# Urukul_FPGA_Config.net
KiCad netlist of a schematic drawn in Altium Designer
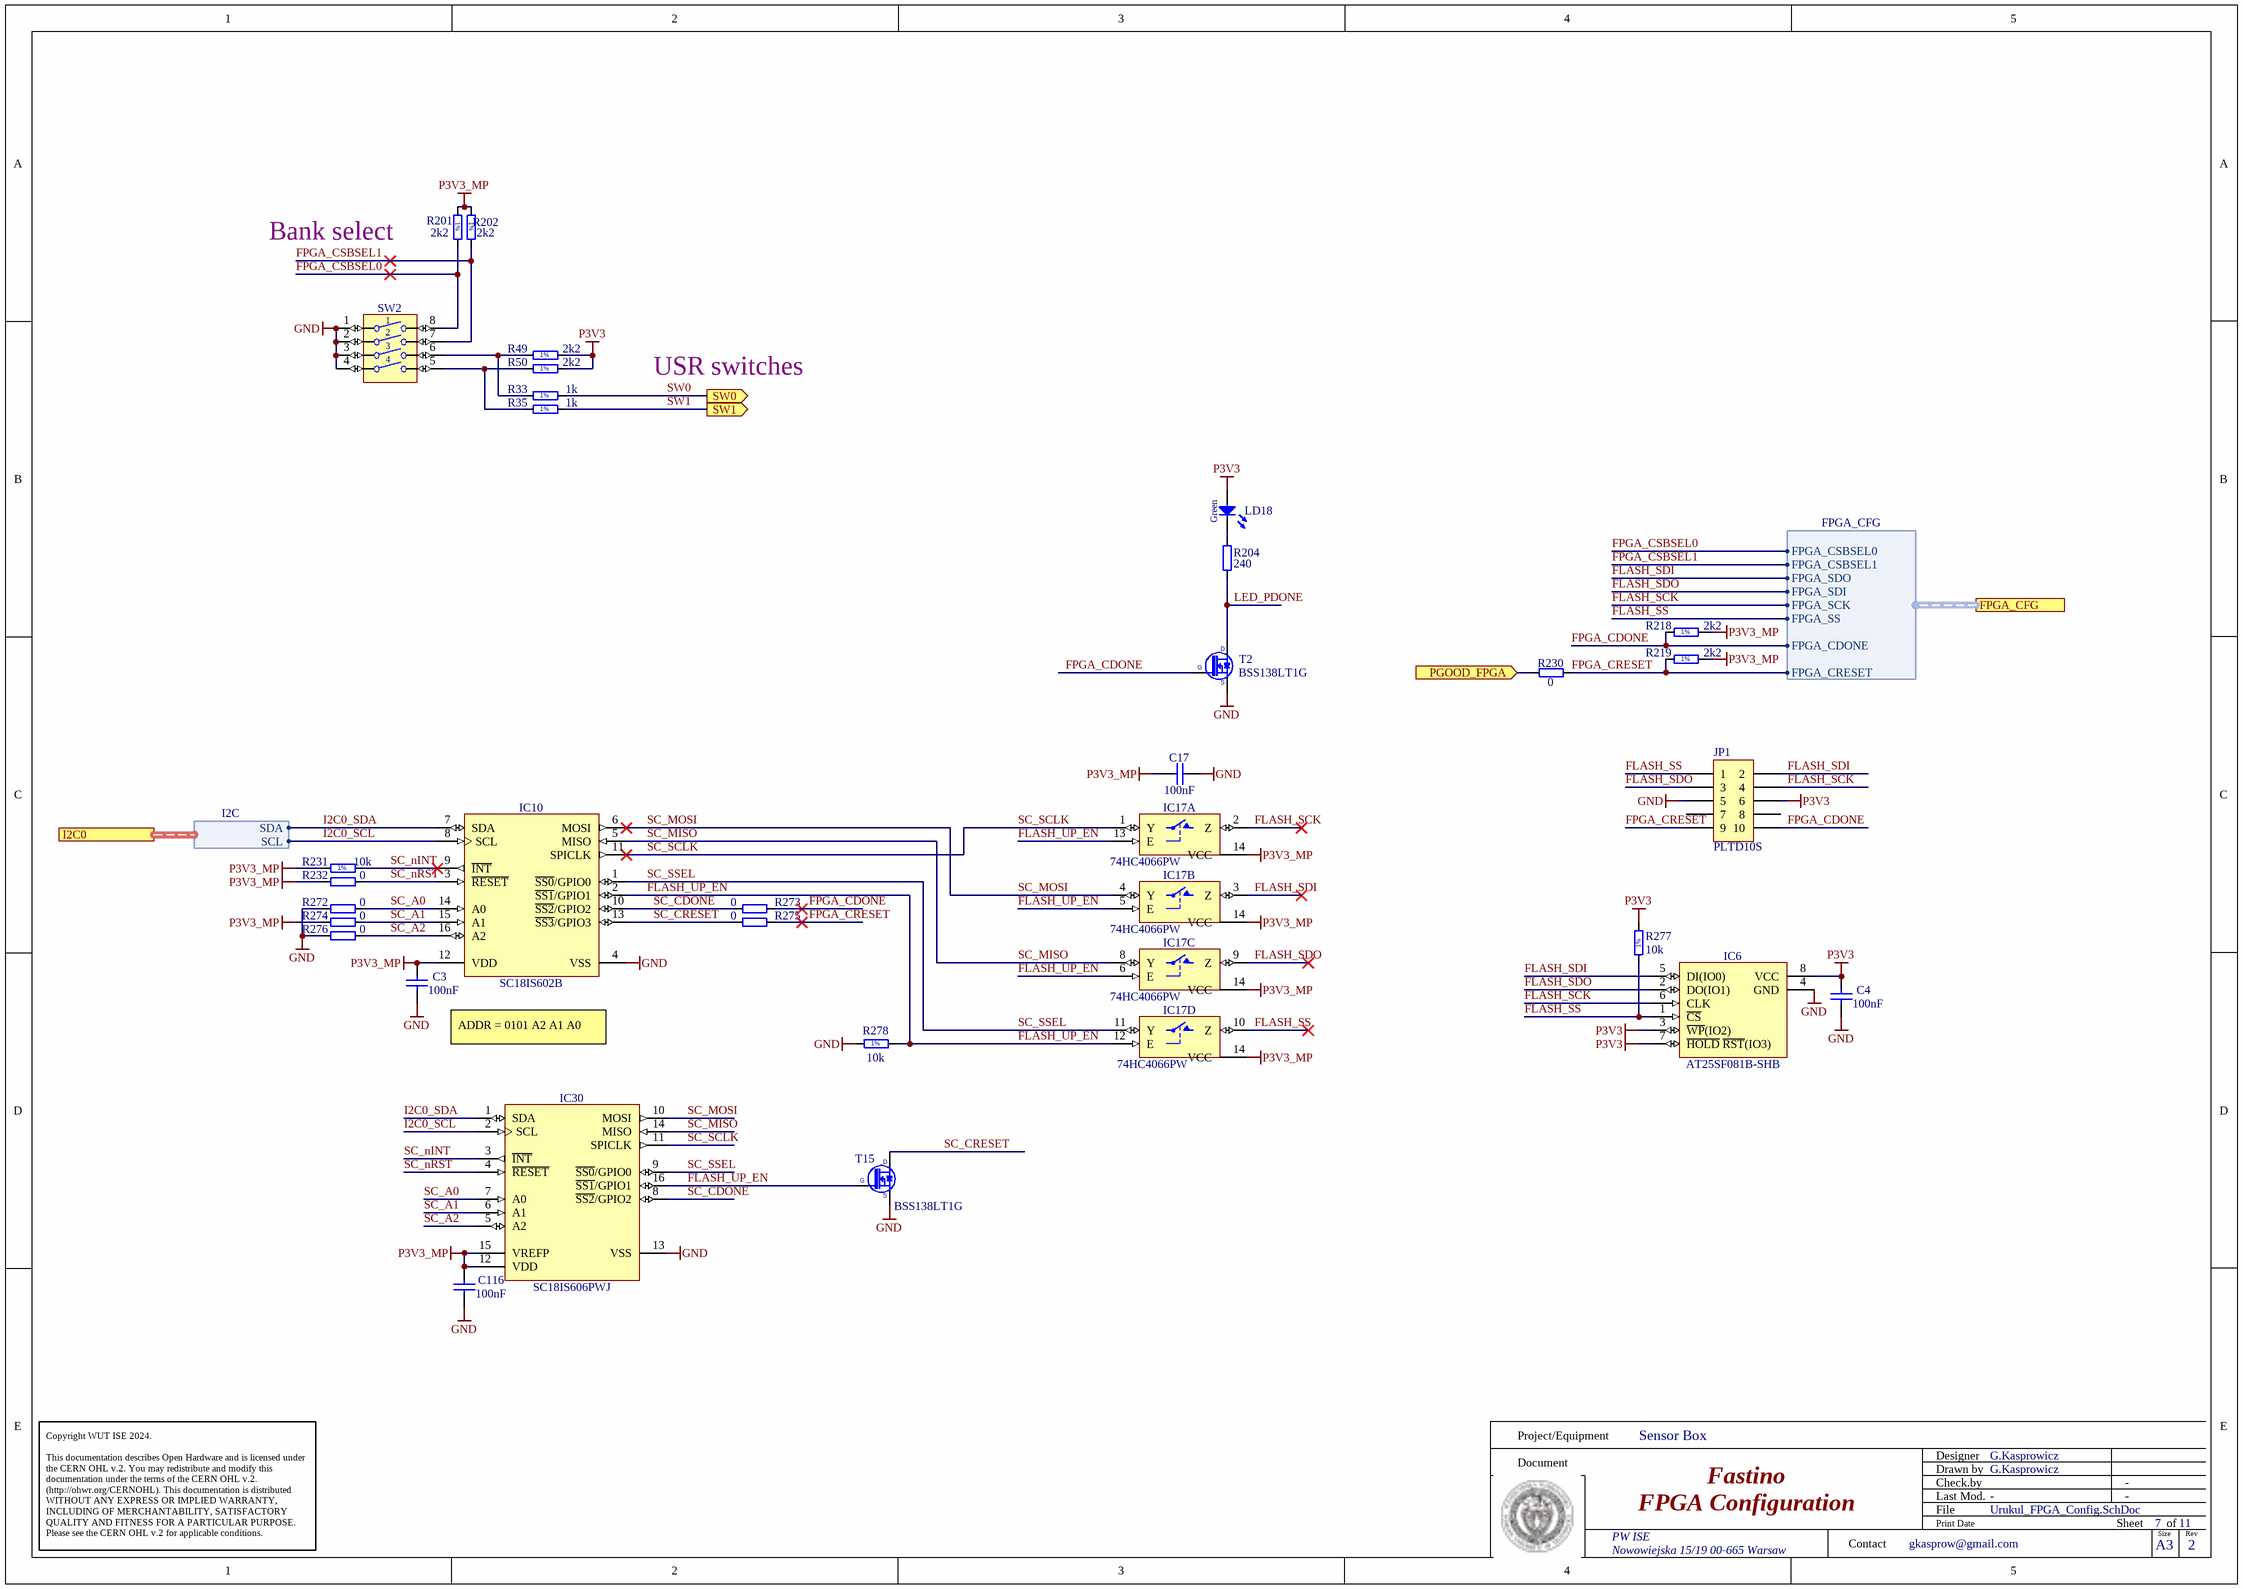
[diagram p0: Urukul_FPGA_Config.SchDoc]

(export (version "E")
  (design (tool "Eeschema 10.0.6"))
  (components
    (comp (ref "C3")
      (value "100nF")
      (footprint "CAPC1005X55N")
      (description "Non-polarised capacitor")
      (fields
        (field (name "PART NUMBER") "CC0402_100NF_16V_10%_X5R")
        (field (name "VOLTAGE") "16V")
        (field (name "AUTHOR") "CERN DEM JLC")
      )
      (libsource (lib "Capacitors") (part "Capacitor - non polarized"))
    )
    (comp (ref "C4")
      (value "100nF")
      (footprint "CAPC1005X55N")
      (description "Non-polarised capacitor")
      (fields
        (field (name "PART NUMBER") "CC0402_100NF_16V_10%_X5R")
        (field (name "VOLTAGE") "16V")
        (field (name "AUTHOR") "CERN DEM JLC")
      )
      (libsource (lib "Capacitors") (part "Capacitor - non polarized"))
    )
    (comp (ref "C17")
      (value "100nF")
      (footprint "CAPC1005X55N")
      (description "Non-polarised capacitor")
      (fields
        (field (name "PART NUMBER") "CC0402_100NF_16V_10%_X5R")
        (field (name "VOLTAGE") "16V")
        (field (name "AUTHOR") "CERN DEM JLC")
      )
      (libsource (lib "Capacitors") (part "Capacitor - non polarized"))
    )
    (comp (ref "C116")
      (value "100nF")
      (footprint "CAPC1005X55N")
      (description "Non-polarised capacitor")
      (fields
        (field (name "PART NUMBER") "CC0402_100NF_16V_10%_X5R")
        (field (name "VOLTAGE") "16V")
        (field (name "AUTHOR") "CERN DEM JLC")
      )
      (libsource (lib "Capacitors") (part "Capacitor - non polarized"))
    )
    (comp (ref "IC6")
      (value "AT25SF081B-SHB")
      (footprint "SOIC127P790X216-8N")
      (description "8M-bit Serial Flash Memory with uniform 4KB sectors and Dual/Quad SPI and QPI")
      (fields (field (name "MANUFACTURER") "Renesas") (field (name "AUTHOR") "GK"))
      (libsource (lib "ICS-logic") (part "MEM_AT25SF081B-SHB"))
    )
    (comp (ref "IC10")
      (value "SC18IS602B")
      (footprint "SOP65P640X110-16N")
      (description "I2C-bus to SPI bridge")
      (fields (field (name "MANUFACTURER") "NXP SEMICONDUCTORS") (field (name "AUTHOR") "CERN DEM MR"))
      (libsource (lib "ICs And Semiconductors") (part "SC18IS602B"))
    )
    (comp (ref "IC17")
      (value "74HC4066PW")
      (footprint "SOP65P640X110-14N")
      (fields (field (name "MANUFACTURER") "NXP SEMICONDUCTORS") (field (name "AUTHOR") "CERN DEM JLC"))
      (libsource (lib "ICs And Semiconductors") (part "4066"))
    )
    (comp (ref "IC30")
      (value "SC18IS606PWJ")
      (footprint "SOP65P640X110-16N")
      (description "I2C-bus to SPI bridge")
      (fields (field (name "MANUFACTURER") "NXP SEMICONDUCTORS") (field (name "AUTHOR") "GK"))
      (libsource (lib "ICS-logic") (part "SC18IS606PWJ"))
    )
    (comp (ref "JP1")
      (value "PLTD10S")
      (footprint "PLTD10S")
      (description "Goldpin 2.54mm, male header")
      (fields (field (name "MANUFACTURER") "Maritex"))
      (libsource (lib "LIBRARY_SCH") (part "CON_2x5 2.54 male SMT"))
    )
    (comp (ref "LD18")
      (value "Green")
      (footprint "LED_AVAGO_HSME-C120")
      (description "LED Green 1C 2A")
      (fields
        (field (name "PART NUMBER") "LED_AVAGO_HSME-C120")
        (field (name "MANUFACTURER") "AVAGO TECHNOLOGIES")
        (field (name "AUTHOR") "CERN DEM JMW")
      )
      (libsource (lib "ICs And Semiconductors") (part "LED Green 1C 2A"))
    )
    (comp (ref "R33")
      (value "1k")
      (footprint "RESC1005X40N")
      (description "Resistor - 1%")
      (fields
        (field (name "PART NUMBER") "R0402_1K_1%_0.0625W_100PPM")
        (field (name "POWER") "0.0625W")
        (field (name "AUTHOR") "CERN DEM JLC")
      )
      (libsource (lib "Resistors") (part "Resistor - 1%"))
    )
    (comp (ref "R35")
      (value "1k")
      (footprint "RESC1005X40N")
      (description "Resistor - 1%")
      (fields
        (field (name "PART NUMBER") "R0402_1K_1%_0.0625W_100PPM")
        (field (name "POWER") "0.0625W")
        (field (name "AUTHOR") "CERN DEM JLC")
      )
      (libsource (lib "Resistors") (part "Resistor - 1%"))
    )
    (comp (ref "R49")
      (value "2k2")
      (footprint "RESC1005X40N")
      (description "Resistor - 1%")
      (fields
        (field (name "PART NUMBER") "R0402_2K2_1%_0.0625W_100PPM")
        (field (name "POWER") "0.0625W")
        (field (name "AUTHOR") "CERN DEM JLC")
      )
      (libsource (lib "Resistors") (part "Resistor - 1%"))
    )
    (comp (ref "R50")
      (value "2k2")
      (footprint "RESC1005X40N")
      (description "Resistor - 1%")
      (fields
        (field (name "PART NUMBER") "R0402_2K2_1%_0.0625W_100PPM")
        (field (name "POWER") "0.0625W")
        (field (name "AUTHOR") "CERN DEM JLC")
      )
      (libsource (lib "Resistors") (part "Resistor - 1%"))
    )
    (comp (ref "R201")
      (value "2k2")
      (footprint "RESC1005X40N")
      (description "Resistor - 1%")
      (fields
        (field (name "PART NUMBER") "R0402_2K2_1%_0.0625W_100PPM")
        (field (name "POWER") "0.0625W")
        (field (name "AUTHOR") "CERN DEM JLC")
      )
      (libsource (lib "Resistors") (part "Resistor - 1%"))
    )
    (comp (ref "R202")
      (value "2k2")
      (footprint "RESC1005X40N")
      (description "Resistor - 1%")
      (fields
        (field (name "PART NUMBER") "R0402_2K2_1%_0.0625W_100PPM")
        (field (name "POWER") "0.0625W")
        (field (name "AUTHOR") "CERN DEM JLC")
      )
      (libsource (lib "Resistors") (part "Resistor - 1%"))
    )
    (comp (ref "R204")
      (value "240")
      (footprint "RESC1005X40N")
      (description "Resistor - 1%")
      (fields
        (field (name "PART NUMBER") "R0402_240R_1%_0.0625W_100PPM")
        (field (name "POWER") "0.0625W")
        (field (name "AUTHOR") "CERN DEM JLC")
      )
      (libsource (lib "Resistors") (part "Resistor - 1%"))
    )
    (comp (ref "R218")
      (value "2k2")
      (footprint "RESC1005X40N")
      (description "Resistor - 1%")
      (fields
        (field (name "PART NUMBER") "R0402_2K2_1%_0.0625W_100PPM")
        (field (name "POWER") "0.0625W")
        (field (name "AUTHOR") "CERN DEM JLC")
      )
      (libsource (lib "Resistors") (part "Resistor - 1%"))
    )
    (comp (ref "R219")
      (value "2k2")
      (footprint "RESC1005X40N")
      (description "Resistor - 1%")
      (fields
        (field (name "PART NUMBER") "R0402_2K2_1%_0.0625W_100PPM")
        (field (name "POWER") "0.0625W")
        (field (name "AUTHOR") "CERN DEM JLC")
      )
      (libsource (lib "Resistors") (part "Resistor - 1%"))
    )
    (comp (ref "R230")
      (value "0")
      (footprint "RESC1005X40N")
      (description "Resistor")
      (fields
        (field (name "PART NUMBER") "R0402_0R_JUMPER")
        (field (name "MANUFACTURER") "GENERIC")
        (field (name "AUTHOR") "CERN DEM JLC")
      )
      (libsource (lib "Resistors") (part "Resistor"))
    )
    (comp (ref "R231")
      (value "10k")
      (footprint "RESC1005X40N")
      (description "Resistor - 1%")
      (fields
        (field (name "PART NUMBER") "R0402_10K_1%_0.0625W_100PPM")
        (field (name "POWER") "0.0625W")
        (field (name "AUTHOR") "CERN DEM JLC")
      )
      (libsource (lib "Resistors") (part "Resistor - 1%"))
    )
    (comp (ref "R232")
      (value "0")
      (footprint "RESC1005X40N")
      (description "Resistor")
      (fields
        (field (name "PART NUMBER") "R0402_0R_JUMPER")
        (field (name "MANUFACTURER") "GENERIC")
        (field (name "AUTHOR") "CERN DEM JLC")
      )
      (libsource (lib "Resistors") (part "Resistor"))
    )
    (comp (ref "R272")
      (value "0")
      (footprint "RESC1005X40N")
      (description "Resistor")
      (fields
        (field (name "PART NUMBER") "R0402_0R_JUMPER")
        (field (name "MANUFACTURER") "GENERIC")
        (field (name "AUTHOR") "CERN DEM JLC")
      )
      (libsource (lib "Resistors") (part "Resistor"))
    )
    (comp (ref "R273")
      (value "0")
      (footprint "RESC1005X40N")
      (description "Resistor")
      (fields
        (field (name "PART NUMBER") "R0402_0R_JUMPER")
        (field (name "MANUFACTURER") "GENERIC")
        (field (name "AUTHOR") "CERN DEM JLC")
      )
      (libsource (lib "Resistors") (part "Resistor"))
    )
    (comp (ref "R274")
      (value "0")
      (footprint "RESC1005X40N")
      (description "Resistor")
      (fields
        (field (name "PART NUMBER") "R0402_0R_JUMPER")
        (field (name "MANUFACTURER") "GENERIC")
        (field (name "AUTHOR") "CERN DEM JLC")
      )
      (libsource (lib "Resistors") (part "Resistor"))
    )
    (comp (ref "R275")
      (value "0")
      (footprint "RESC1005X40N")
      (description "Resistor")
      (fields
        (field (name "PART NUMBER") "R0402_0R_JUMPER")
        (field (name "MANUFACTURER") "GENERIC")
        (field (name "AUTHOR") "CERN DEM JLC")
      )
      (libsource (lib "Resistors") (part "Resistor"))
    )
    (comp (ref "R276")
      (value "0")
      (footprint "RESC1005X40N")
      (description "Resistor")
      (fields
        (field (name "PART NUMBER") "R0402_0R_JUMPER")
        (field (name "MANUFACTURER") "GENERIC")
        (field (name "AUTHOR") "CERN DEM JLC")
      )
      (libsource (lib "Resistors") (part "Resistor"))
    )
    (comp (ref "R277")
      (value "10k")
      (footprint "RESC1005X40N")
      (description "Resistor - 1%")
      (fields
        (field (name "PART NUMBER") "R0402_10K_1%_0.0625W_100PPM")
        (field (name "POWER") "0.0625W")
        (field (name "AUTHOR") "CERN DEM JLC")
      )
      (libsource (lib "Resistors") (part "Resistor - 1%"))
    )
    (comp (ref "R278")
      (value "10k")
      (footprint "RESC1005X40N")
      (description "Resistor - 1%")
      (fields
        (field (name "PART NUMBER") "R0402_10K_1%_0.0625W_100PPM")
        (field (name "POWER") "0.0625W")
        (field (name "AUTHOR") "CERN DEM JLC")
      )
      (libsource (lib "Resistors") (part "Resistor - 1%"))
    )
    (comp (ref "SW2")
      (value "Switch")
      (footprint "SW_TYCO_1571983-4")
      (description "4 Ways SPST DIP Switch")
      (fields
        (field (name "PART NUMBER") "SW_TYCO_1571983-4")
        (field (name "MANUFACTURER") "TYCO")
        (field (name "AUTHOR") "CERN DEM JLC")
      )
      (libsource (lib "Eletro-mechanical") (part "SW 4x SPST DIP Switch"))
    )
    (comp (ref "T2")
      (value "BSS138LT1G")
      (footprint "SOT95P240X110-3N")
      (description "N-CHANNEL MOSFET WITH DIODE")
      (fields (field (name "MANUFACTURER") "ON SEMICONDUCTOR") (field (name "AUTHOR") "CERN DEM JLC"))
      (libsource (lib "ICs And Semiconductors") (part "N-MOSFET-D 1G 2S 3D"))
    )
    (comp (ref "T15")
      (value "BSS138LT1G")
      (footprint "SOT95P240X110-3N")
      (description "N-CHANNEL MOSFET WITH DIODE")
      (fields (field (name "MANUFACTURER") "ON SEMICONDUCTOR") (field (name "AUTHOR") "CERN DEM JLC"))
      (libsource (lib "ICs And Semiconductors") (part "N-MOSFET-D 1G 2S 3D"))
    )
  )
  (nets
    (net (code "3") (name "/FLASH_SCK") (class "Default")
      (node (ref "IC17") (pin "2") (pinfunction "Z_2") (pintype "bidirectional"))
      (node (ref "IC6") (pin "6") (pinfunction "CLK_6") (pintype "input"))
      (node (ref "JP1") (pin "4") (pinfunction "4_4") (pintype "passive"))
    )
    (net (code "4") (name "/FLASH_SDI") (class "Default")
      (node (ref "IC17") (pin "3") (pinfunction "Z_3") (pintype "bidirectional"))
      (node (ref "IC6") (pin "5") (pinfunction "DI(IO0)_5") (pintype "bidirectional"))
      (node (ref "JP1") (pin "2") (pinfunction "2_2") (pintype "passive"))
    )
    (net (code "5") (name "/FLASH_SDO") (class "Default")
      (node (ref "IC17") (pin "9") (pinfunction "Z_9") (pintype "bidirectional"))
      (node (ref "IC6") (pin "2") (pinfunction "DO(IO1)_2") (pintype "bidirectional"))
      (node (ref "JP1") (pin "3") (pinfunction "3_3") (pintype "passive"))
    )
    (net (code "6") (name "/FLASH_SS") (class "Default")
      (node (ref "IC17") (pin "10") (pinfunction "Z_10") (pintype "bidirectional"))
      (node (ref "IC6") (pin "1") (pinfunction "~{CS}_1") (pintype "input"))
      (node (ref "JP1") (pin "1") (pinfunction "1_1") (pintype "passive"))
      (node (ref "R277") (pin "1") (pinfunction "1_1") (pintype "passive"))
    )
    (net (code "7") (name "/FLASH_UP_EN") (class "Default")
      (node (ref "IC10") (pin "2") (pinfunction "~{SS1}/GPIO1_2") (pintype "bidirectional"))
      (node (ref "IC17") (pin "12") (pinfunction "E_12") (pintype "input"))
      (node (ref "IC17") (pin "13") (pinfunction "E_13") (pintype "input"))
      (node (ref "IC17") (pin "5") (pinfunction "E_5") (pintype "input"))
      (node (ref "IC17") (pin "6") (pinfunction "E_6") (pintype "input"))
      (node (ref "IC30") (pin "16") (pinfunction "~{SS1}/GPIO1_16") (pintype "bidirectional"))
      (node (ref "R278") (pin "2") (pinfunction "2_2") (pintype "passive"))
      (node (ref "T15") (pin "1") (pinfunction "G_1") (pintype "passive"))
    )
    (net (code "8") (name "/FPGA_CDONE") (class "Default")
      (node (ref "JP1") (pin "10") (pinfunction "10_10") (pintype "passive"))
      (node (ref "R218") (pin "1") (pinfunction "1_1") (pintype "passive"))
      (node (ref "R273") (pin "1") (pinfunction "1_1") (pintype "passive"))
      (node (ref "T2") (pin "1") (pinfunction "G_1") (pintype "passive"))
    )
    (net (code "9") (name "/FPGA_CRESET") (class "Default")
      (node (ref "JP1") (pin "9") (pinfunction "9_9") (pintype "passive"))
      (node (ref "R219") (pin "1") (pinfunction "1_1") (pintype "passive"))
      (node (ref "R230") (pin "2") (pinfunction "2_2") (pintype "passive"))
      (node (ref "R275") (pin "1") (pinfunction "1_1") (pintype "passive"))
    )
    (net (code "10") (name "/FPGA_CSBSEL0") (class "Default")
      (node (ref "R201") (pin "2") (pinfunction "2_2") (pintype "passive"))
      (node (ref "SW2") (pin "8") (pinfunction "8_8") (pintype "bidirectional"))
    )
    (net (code "11") (name "/FPGA_CSBSEL1") (class "Default")
      (node (ref "R202") (pin "2") (pinfunction "2_2") (pintype "passive"))
      (node (ref "SW2") (pin "7") (pinfunction "7_7") (pintype "bidirectional"))
    )
    (net (code "12") (name "/I2C0_SCL") (class "Default")
      (node (ref "IC10") (pin "8") (pinfunction "SCL_8") (pintype "input"))
      (node (ref "IC30") (pin "2") (pinfunction "SCL_2") (pintype "input"))
    )
    (net (code "13") (name "/I2C0_SDA") (class "Default")
      (node (ref "IC10") (pin "7") (pinfunction "SDA_7") (pintype "bidirectional"))
      (node (ref "IC30") (pin "1") (pinfunction "SDA_1") (pintype "bidirectional"))
    )
    (net (code "14") (name "/LED_PDONE") (class "Default")
      (node (ref "R204") (pin "1") (pinfunction "1_1") (pintype "passive"))
      (node (ref "T2") (pin "3") (pinfunction "D_3") (pintype "passive"))
    )
    (net (code "15") (name "/PGOOD_FPGA") (class "Default")
      (node (ref "R230") (pin "1") (pinfunction "1_1") (pintype "passive"))
    )
    (net (code "16") (name "/SC_A0") (class "Default")
      (node (ref "IC10") (pin "14") (pinfunction "A0_14") (pintype "input"))
      (node (ref "IC30") (pin "7") (pinfunction "A0_7") (pintype "input"))
      (node (ref "R272") (pin "1") (pinfunction "1_1") (pintype "passive"))
    )
    (net (code "17") (name "/SC_A1") (class "Default")
      (node (ref "IC10") (pin "15") (pinfunction "A1_15") (pintype "input"))
      (node (ref "IC30") (pin "6") (pinfunction "A1_6") (pintype "input"))
      (node (ref "R274") (pin "1") (pinfunction "1_1") (pintype "passive"))
    )
    (net (code "18") (name "/SC_A2") (class "Default")
      (node (ref "IC10") (pin "16") (pinfunction "A2_16") (pintype "bidirectional"))
      (node (ref "IC30") (pin "5") (pinfunction "A2_5") (pintype "bidirectional"))
      (node (ref "R276") (pin "1") (pinfunction "1_1") (pintype "passive"))
    )
    (net (code "19") (name "/SC_CDONE") (class "Default")
      (node (ref "IC10") (pin "10") (pinfunction "~{SS2}/GPIO2_10") (pintype "bidirectional"))
      (node (ref "IC30") (pin "8") (pinfunction "~{SS2}/GPIO2_8") (pintype "bidirectional"))
      (node (ref "R273") (pin "2") (pinfunction "2_2") (pintype "passive"))
    )
    (net (code "20") (name "/SC_CRESET") (class "Default")
      (node (ref "IC10") (pin "13") (pinfunction "~{SS3}/GPIO3_13") (pintype "bidirectional"))
      (node (ref "R275") (pin "2") (pinfunction "2_2") (pintype "passive"))
      (node (ref "T15") (pin "3") (pinfunction "D_3") (pintype "passive"))
    )
    (net (code "21") (name "/SC_MISO") (class "Default")
      (node (ref "IC10") (pin "5") (pinfunction "MISO_5") (pintype "input"))
      (node (ref "IC17") (pin "8") (pinfunction "Y_8") (pintype "bidirectional"))
      (node (ref "IC30") (pin "14") (pinfunction "MISO_14") (pintype "input"))
    )
    (net (code "22") (name "/SC_MOSI") (class "Default")
      (node (ref "IC10") (pin "6") (pinfunction "MOSI_6") (pintype "output"))
      (node (ref "IC17") (pin "4") (pinfunction "Y_4") (pintype "bidirectional"))
      (node (ref "IC30") (pin "10") (pinfunction "MOSI_10") (pintype "output"))
    )
    (net (code "23") (name "/SC_SCLK") (class "Default")
      (node (ref "IC10") (pin "11") (pinfunction "SPICLK_11") (pintype "output"))
      (node (ref "IC17") (pin "1") (pinfunction "Y_1") (pintype "bidirectional"))
      (node (ref "IC30") (pin "11") (pinfunction "SPICLK_11") (pintype "output"))
    )
    (net (code "24") (name "/SC_SSEL") (class "Default")
      (node (ref "IC10") (pin "1") (pinfunction "~{SS0}/GPIO0_1") (pintype "bidirectional"))
      (node (ref "IC17") (pin "11") (pinfunction "Y_11") (pintype "bidirectional"))
      (node (ref "IC30") (pin "9") (pinfunction "~{SS0}/GPIO0_9") (pintype "bidirectional"))
    )
    (net (code "25") (name "/SC_nINT") (class "Default")
      (node (ref "IC10") (pin "9") (pinfunction "~{INT}_9") (pintype "output"))
      (node (ref "IC30") (pin "3") (pinfunction "~{INT}_3") (pintype "output"))
      (node (ref "R231") (pin "2") (pinfunction "2_2") (pintype "passive"))
    )
    (net (code "26") (name "/SC_nRST") (class "Default")
      (node (ref "IC10") (pin "3") (pinfunction "~{RESET}_3") (pintype "input"))
      (node (ref "IC30") (pin "4") (pinfunction "~{RESET}_4") (pintype "input"))
      (node (ref "R232") (pin "1") (pinfunction "1_1") (pintype "passive"))
    )
    (net (code "27") (name "/SW0") (class "Default")
      (node (ref "R33") (pin "2") (pinfunction "2_2") (pintype "passive"))
    )
    (net (code "28") (name "/SW1") (class "Default")
      (node (ref "R35") (pin "2") (pinfunction "2_2") (pintype "passive"))
    )
    (net (code "31") (name "GND") (class "Default")
      (node (ref "C116") (pin "1") (pinfunction "1_1") (pintype "passive"))
      (node (ref "C17") (pin "2") (pinfunction "2_2") (pintype "passive"))
      (node (ref "C3") (pin "1") (pinfunction "1_1") (pintype "passive"))
      (node (ref "C4") (pin "1") (pinfunction "1_1") (pintype "passive"))
      (node (ref "IC10") (pin "4") (pinfunction "VSS_4") (pintype "power_in"))
      (node (ref "IC17") (pin "7") (pinfunction "GND_7") (pintype "power_in"))
      (node (ref "IC30") (pin "13") (pinfunction "VSS_13") (pintype "power_in"))
      (node (ref "IC6") (pin "4") (pinfunction "GND_4") (pintype "power_in"))
      (node (ref "JP1") (pin "5") (pinfunction "5_5") (pintype "passive"))
      (node (ref "R272") (pin "2") (pinfunction "2_2") (pintype "passive"))
      (node (ref "R276") (pin "2") (pinfunction "2_2") (pintype "passive"))
      (node (ref "R278") (pin "1") (pinfunction "1_1") (pintype "passive"))
      (node (ref "SW2") (pin "1") (pinfunction "1_1") (pintype "bidirectional"))
      (node (ref "SW2") (pin "2") (pinfunction "2_2") (pintype "bidirectional"))
      (node (ref "SW2") (pin "3") (pinfunction "3_3") (pintype "bidirectional"))
      (node (ref "SW2") (pin "4") (pinfunction "4_4") (pintype "bidirectional"))
      (node (ref "T15") (pin "2") (pinfunction "S_2") (pintype "passive"))
      (node (ref "T2") (pin "2") (pinfunction "S_2") (pintype "passive"))
    )
    (net (code "32") (name "Net-(LD18-C)") (class "Default")
      (node (ref "LD18") (pin "1") (pinfunction "C_1") (pintype "passive"))
      (node (ref "R204") (pin "2") (pinfunction "2_2") (pintype "passive"))
    )
    (net (code "33") (name "Net-(R33-Pad1)") (class "Default")
      (node (ref "R33") (pin "1") (pinfunction "1_1") (pintype "passive"))
      (node (ref "R49") (pin "1") (pinfunction "1_1") (pintype "passive"))
      (node (ref "SW2") (pin "6") (pinfunction "6_6") (pintype "bidirectional"))
    )
    (net (code "34") (name "Net-(R35-Pad1)") (class "Default")
      (node (ref "R35") (pin "1") (pinfunction "1_1") (pintype "passive"))
      (node (ref "R50") (pin "1") (pinfunction "1_1") (pintype "passive"))
      (node (ref "SW2") (pin "5") (pinfunction "5_5") (pintype "bidirectional"))
    )
    (net (code "35") (name "P3V3") (class "Default")
      (node (ref "C4") (pin "2") (pinfunction "2_2") (pintype "passive"))
      (node (ref "IC6") (pin "3") (pinfunction "~{WP}(IO2)_3") (pintype "bidirectional"))
      (node (ref "IC6") (pin "7") (pinfunction "~{HOLD}_~{RST}(IO3)_7") (pintype "bidirectional"))
      (node (ref "IC6") (pin "8") (pinfunction "VCC_8") (pintype "power_in"))
      (node (ref "JP1") (pin "6") (pinfunction "6_6") (pintype "passive"))
      (node (ref "LD18") (pin "2") (pinfunction "A_2") (pintype "passive"))
      (node (ref "R277") (pin "2") (pinfunction "2_2") (pintype "passive"))
      (node (ref "R49") (pin "2") (pinfunction "2_2") (pintype "passive"))
      (node (ref "R50") (pin "2") (pinfunction "2_2") (pintype "passive"))
    )
    (net (code "36") (name "P3V3_MP") (class "Default")
      (node (ref "C116") (pin "2") (pinfunction "2_2") (pintype "passive"))
      (node (ref "C17") (pin "1") (pinfunction "1_1") (pintype "passive"))
      (node (ref "C3") (pin "2") (pinfunction "2_2") (pintype "passive"))
      (node (ref "IC10") (pin "12") (pinfunction "VDD_12") (pintype "power_in"))
      (node (ref "IC17") (pin "14") (pinfunction "VCC_14") (pintype "power_in"))
      (node (ref "IC30") (pin "12") (pinfunction "VDD_12") (pintype "power_in"))
      (node (ref "IC30") (pin "15") (pinfunction "VREFP_15") (pintype "power_in"))
      (node (ref "R201") (pin "1") (pinfunction "1_1") (pintype "passive"))
      (node (ref "R202") (pin "1") (pinfunction "1_1") (pintype "passive"))
      (node (ref "R218") (pin "2") (pinfunction "2_2") (pintype "passive"))
      (node (ref "R219") (pin "2") (pinfunction "2_2") (pintype "passive"))
      (node (ref "R231") (pin "1") (pinfunction "1_1") (pintype "passive"))
      (node (ref "R232") (pin "2") (pinfunction "2_2") (pintype "passive"))
      (node (ref "R274") (pin "2") (pinfunction "2_2") (pintype "passive"))
    )
    (net (code "37") (name "unconnected-(JP1-Pad7)") (class "Default")
      (node (ref "JP1") (pin "7") (pinfunction "7_7") (pintype "passive"))
    )
    (net (code "38") (name "unconnected-(JP1-Pad8)") (class "Default")
      (node (ref "JP1") (pin "8") (pinfunction "8_8") (pintype "passive"))
    )
  )
)
